# Battery_charger.net
KiCad netlist of a schematic drawn in Altium Designer
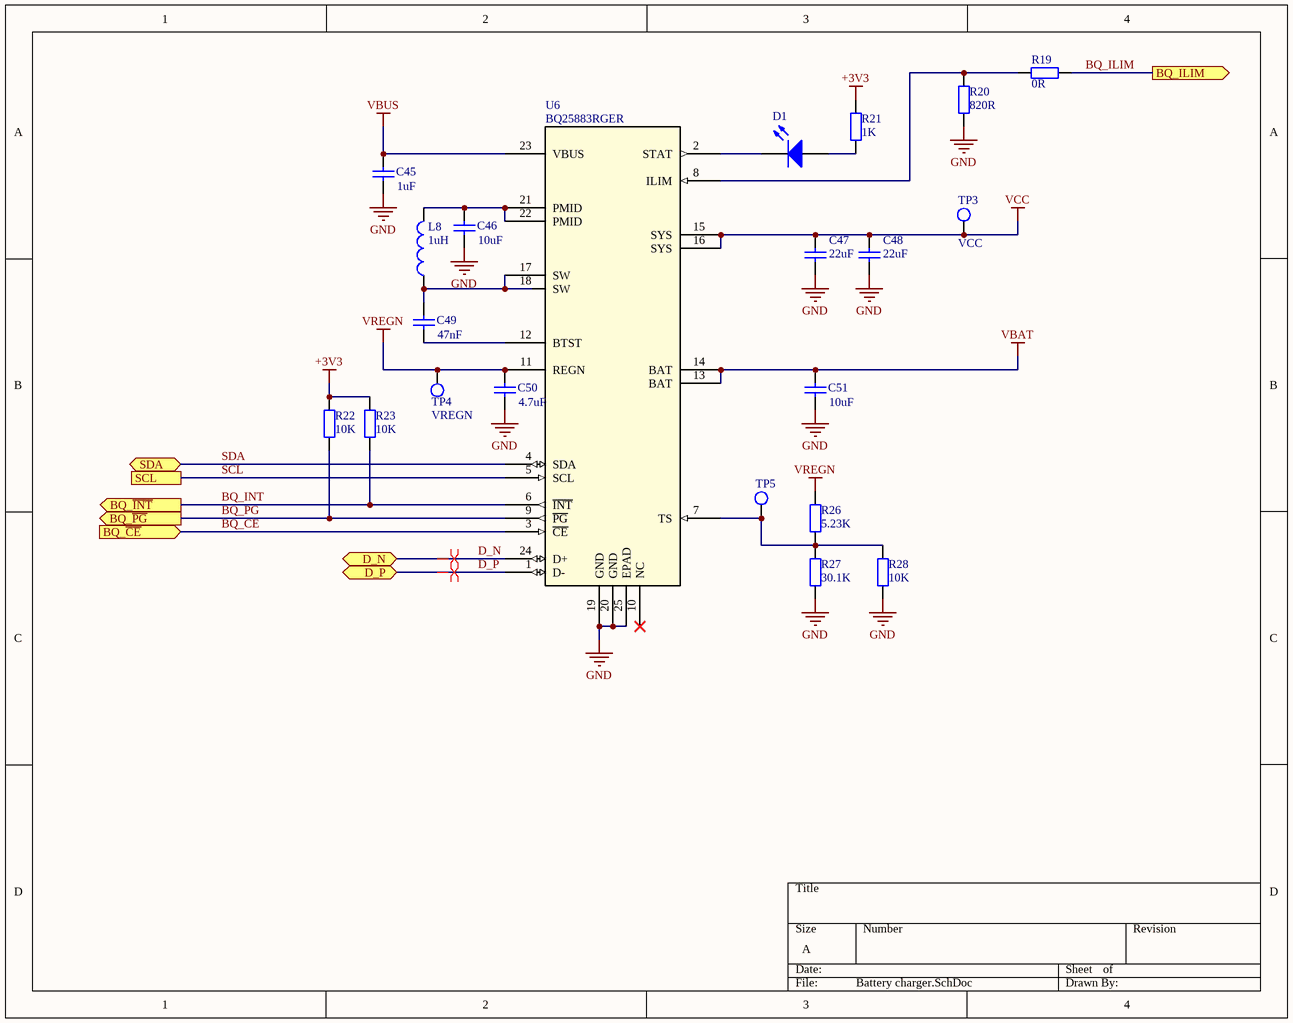
[diagram p0: Battery charger.SchDoc]

(export (version "E")
  (design (tool "Eeschema 10.0.6"))
  (components
    (comp (ref "C45")
      (value "1uF")
      (footprint "0402")
      (description "Capacitor")
      (fields (field (name "PUBLISHER") "Altium Limited"))
      (libsource (lib "Miscellaneous Devices") (part "Cap"))
    )
    (comp (ref "C46")
      (value "10uF")
      (footprint "0402")
      (description "Capacitor")
      (fields (field (name "PUBLISHER") "Altium Limited"))
      (libsource (lib "Miscellaneous Devices") (part "Cap"))
    )
    (comp (ref "C47")
      (value "22uF")
      (footprint "0402")
      (description "Capacitor")
      (fields (field (name "Comment") "Cap") (field (name "PUBLISHER") "Altium Limited"))
      (libsource (lib "Miscellaneous Devices") (part "Cap"))
    )
    (comp (ref "C48")
      (value "22uF")
      (footprint "0402")
      (description "Capacitor")
      (fields (field (name "Comment") "Cap") (field (name "PUBLISHER") "Altium Limited"))
      (libsource (lib "Miscellaneous Devices") (part "Cap"))
    )
    (comp (ref "C49")
      (value "47nF")
      (footprint "0402")
      (description "Capacitor")
      (fields (field (name "PUBLISHER") "Altium Limited"))
      (libsource (lib "Miscellaneous Devices") (part "Cap"))
    )
    (comp (ref "C50")
      (value "4.7uF")
      (footprint "0402")
      (description "Capacitor")
      (fields (field (name "PUBLISHER") "Altium Limited"))
      (libsource (lib "Miscellaneous Devices") (part "Cap"))
    )
    (comp (ref "C51")
      (value "10uF")
      (footprint "0402")
      (description "Capacitor")
      (fields (field (name "PUBLISHER") "Altium Limited"))
      (libsource (lib "Miscellaneous Devices") (part "Cap"))
    )
    (comp (ref "D1")
      (value "SML-D12P8WT86")
      (description "Light-Emitting Diode")
      (libsource (lib "Simulation Generic Components") (part "LED"))
    )
    (comp (ref "L8")
      (value "1uH")
      (footprint "0402-A")
      (description "Inductor")
      (fields (field (name "PUBLISHER") "Altium Limited"))
      (libsource (lib "Miscellaneous Devices") (part "Inductor"))
    )
    (comp (ref "R19")
      (value "0R")
      (footprint "SMD-0402-RES")
      (description "Resistor")
      (fields (field (name "PUBLISHER") "Altium Limited"))
      (libsource (lib "") (part "Res2_2"))
    )
    (comp (ref "R20")
      (value "820R")
      (footprint "SMD-0402-RES")
      (description "Resistor")
      (fields (field (name "PUBLISHER") "Altium Limited"))
      (libsource (lib "Miscellaneous Devices") (part "Res2"))
    )
    (comp (ref "R21")
      (value "1K")
      (footprint "SMD-0402-RES")
      (description "Resistor")
      (fields (field (name "PUBLISHER") "Altium Limited"))
      (libsource (lib "") (part "Res2_1"))
    )
    (comp (ref "R22")
      (value "10K")
      (footprint "SMD-0402-RES")
      (description "Resistor")
      (fields (field (name "PUBLISHER") "Altium Limited"))
      (libsource (lib "Miscellaneous Devices") (part "Res2"))
    )
    (comp (ref "R23")
      (value "10K")
      (footprint "SMD-0402-RES")
      (description "Resistor")
      (fields (field (name "PUBLISHER") "Altium Limited"))
      (libsource (lib "Miscellaneous Devices") (part "Res2"))
    )
    (comp (ref "R26")
      (value "5.23K")
      (footprint "SMD-0402-RES")
      (description "Resistor")
      (fields (field (name "PUBLISHER") "Altium Limited"))
      (libsource (lib "Miscellaneous Devices") (part "Res2"))
    )
    (comp (ref "R27")
      (value "30.1K")
      (footprint "SMD-0402-RES")
      (description "Resistor")
      (fields (field (name "PUBLISHER") "Altium Limited"))
      (libsource (lib "Miscellaneous Devices") (part "Res2"))
    )
    (comp (ref "R28")
      (value "10K")
      (footprint "SMD-0402-RES")
      (description "Resistor")
      (fields (field (name "PUBLISHER") "Altium Limited"))
      (libsource (lib "Miscellaneous Devices") (part "Res2"))
    )
    (comp (ref "TP3")
      (value "VCC")
      (footprint "testpoint 1 mm")
      (libsource (lib "Schematic_library") (part "testpoint"))
    )
    (comp (ref "TP4")
      (value "VREGN")
      (footprint "testpoint 1 mm")
      (libsource (lib "Schematic_library") (part "testpoint"))
    )
    (comp (ref "TP5")
      (value "VREGN")
      (footprint "testpoint 1 mm")
      (libsource (lib "Schematic_library") (part "testpoint"))
    )
    (comp (ref "U6")
      (value "BQ25883RGER")
      (footprint "BQ25883RGER")
      (fields (field (name "COPYRIGHT") "Copyright (C) 2025 Ultra Librarian. All rights reserved."))
      (libsource (lib "Schematic_library") (part "BQ25883RGER"))
    )
  )
  (nets
    (net (code "1") (name "+3V3") (class "Default")
      (node (ref "R21") (pin "1") (pinfunction "1_1") (pintype "passive"))
      (node (ref "R22") (pin "2") (pinfunction "2_2") (pintype "passive"))
      (node (ref "R23") (pin "2") (pinfunction "2_2") (pintype "passive"))
    )
    (net (code "2") (name "/BQ_CE") (class "Default")
      (node (ref "U6") (pin "3") (pinfunction "~{CE}_3") (pintype "input"))
    )
    (net (code "3") (name "/BQ_ILIM") (class "Default")
      (node (ref "R19") (pin "2") (pinfunction "2_2") (pintype "passive"))
    )
    (net (code "4") (name "/BQ_INT") (class "Default")
      (node (ref "R23") (pin "1") (pinfunction "1_1") (pintype "passive"))
      (node (ref "U6") (pin "6") (pinfunction "~{INT}_6") (pintype "output"))
    )
    (net (code "5") (name "/BQ_PG") (class "Default")
      (node (ref "R22") (pin "1") (pinfunction "1_1") (pintype "passive"))
      (node (ref "U6") (pin "9") (pinfunction "~{PG}_9") (pintype "output"))
    )
    (net (code "6") (name "/D_N") (class "Default")
      (node (ref "U6") (pin "24") (pinfunction "D+_24") (pintype "bidirectional"))
    )
    (net (code "7") (name "/D_P") (class "Default")
      (node (ref "U6") (pin "1") (pinfunction "D-_1") (pintype "bidirectional"))
    )
    (net (code "8") (name "/SCL") (class "Default")
      (node (ref "U6") (pin "5") (pinfunction "SCL_5") (pintype "input"))
    )
    (net (code "9") (name "/SDA") (class "Default")
      (node (ref "U6") (pin "4") (pinfunction "SDA_4") (pintype "bidirectional"))
    )
    (net (code "10") (name "GND") (class "Default")
      (node (ref "C45") (pin "1") (pinfunction "1_1") (pintype "passive"))
      (node (ref "C46") (pin "1") (pinfunction "1_1") (pintype "passive"))
      (node (ref "C47") (pin "1") (pinfunction "1_1") (pintype "passive"))
      (node (ref "C48") (pin "1") (pinfunction "1_1") (pintype "passive"))
      (node (ref "C50") (pin "1") (pinfunction "1_1") (pintype "passive"))
      (node (ref "C51") (pin "1") (pinfunction "1_1") (pintype "passive"))
      (node (ref "R20") (pin "1") (pinfunction "1_1") (pintype "passive"))
      (node (ref "R27") (pin "1") (pinfunction "1_1") (pintype "passive"))
      (node (ref "R28") (pin "1") (pinfunction "1_1") (pintype "passive"))
      (node (ref "U6") (pin "19") (pinfunction "GND_19") (pintype "power_in"))
      (node (ref "U6") (pin "20") (pinfunction "GND_20") (pintype "power_in"))
      (node (ref "U6") (pin "25") (pinfunction "EPAD_25") (pintype "power_in"))
    )
    (net (code "11") (name "Net-(C46-Pad2)") (class "Default")
      (node (ref "C46") (pin "2") (pinfunction "2_2") (pintype "passive"))
      (node (ref "L8") (pin "2") (pinfunction "2_2") (pintype "passive"))
      (node (ref "U6") (pin "21") (pinfunction "PMID_21") (pintype "power_in"))
      (node (ref "U6") (pin "22") (pinfunction "PMID_22") (pintype "power_in"))
    )
    (net (code "12") (name "Net-(C49-Pad2)") (class "Default")
      (node (ref "C49") (pin "2") (pinfunction "2_2") (pintype "passive"))
      (node (ref "L8") (pin "1") (pinfunction "1_1") (pintype "passive"))
      (node (ref "U6") (pin "17") (pinfunction "SW_17") (pintype "power_in"))
      (node (ref "U6") (pin "18") (pinfunction "SW_18") (pintype "power_in"))
    )
    (net (code "13") (name "Net-(D1-A)") (class "Default")
      (node (ref "D1") (pin "1") (pinfunction "A_1") (pintype "passive"))
      (node (ref "R21") (pin "2") (pinfunction "2_2") (pintype "passive"))
    )
    (net (code "14") (name "Net-(D1-K)") (class "Default")
      (node (ref "D1") (pin "2") (pinfunction "K_2") (pintype "passive"))
      (node (ref "U6") (pin "2") (pinfunction "STAT_2") (pintype "output"))
    )
    (net (code "15") (name "Net-(U6-BTST)") (class "Default")
      (node (ref "C49") (pin "1") (pinfunction "1_1") (pintype "passive"))
      (node (ref "U6") (pin "12") (pinfunction "BTST_12") (pintype "power_in"))
    )
    (net (code "16") (name "Net-(U6-ILIM)") (class "Default")
      (node (ref "R19") (pin "1") (pinfunction "1_1") (pintype "passive"))
      (node (ref "R20") (pin "2") (pinfunction "2_2") (pintype "passive"))
      (node (ref "U6") (pin "8") (pinfunction "ILIM_8") (pintype "input"))
    )
    (net (code "17") (name "Net-(U6-TS)") (class "Default")
      (node (ref "R26") (pin "1") (pinfunction "1_1") (pintype "passive"))
      (node (ref "R27") (pin "2") (pinfunction "2_2") (pintype "passive"))
      (node (ref "R28") (pin "2") (pinfunction "2_2") (pintype "passive"))
      (node (ref "TP5") (pin "1") (pinfunction "1_1") (pintype "passive"))
      (node (ref "U6") (pin "7") (pinfunction "TS_7") (pintype "input"))
    )
    (net (code "18") (name "VBAT") (class "Default")
      (node (ref "C51") (pin "2") (pinfunction "2_2") (pintype "passive"))
      (node (ref "U6") (pin "13") (pinfunction "BAT_13") (pintype "power_in"))
      (node (ref "U6") (pin "14") (pinfunction "BAT_14") (pintype "power_in"))
    )
    (net (code "19") (name "VBUS") (class "Default")
      (node (ref "C45") (pin "2") (pinfunction "2_2") (pintype "passive"))
      (node (ref "U6") (pin "23") (pinfunction "VBUS_23") (pintype "power_in"))
    )
    (net (code "20") (name "VCC") (class "Default")
      (node (ref "C47") (pin "2") (pinfunction "2_2") (pintype "passive"))
      (node (ref "C48") (pin "2") (pinfunction "2_2") (pintype "passive"))
      (node (ref "TP3") (pin "1") (pinfunction "1_1") (pintype "passive"))
      (node (ref "U6") (pin "15") (pinfunction "SYS_15") (pintype "power_in"))
      (node (ref "U6") (pin "16") (pinfunction "SYS_16") (pintype "power_in"))
    )
    (net (code "21") (name "VREGN") (class "Default")
      (node (ref "C50") (pin "2") (pinfunction "2_2") (pintype "passive"))
      (node (ref "R26") (pin "2") (pinfunction "2_2") (pintype "passive"))
      (node (ref "TP4") (pin "1") (pinfunction "1_1") (pintype "passive"))
      (node (ref "U6") (pin "11") (pinfunction "REGN_11") (pintype "power_in"))
    )
    (net (code "22") (name "unconnected-(U6-NC-Pad10)") (class "Default")
      (node (ref "U6") (pin "10") (pinfunction "NC_10") (pintype "passive+no_connect"))
    )
  )
)
